# 9-Pin_Mini_DIN_Breakout_PCB_v1.net
KiCad netlist of a schematic drawn in EAGLE
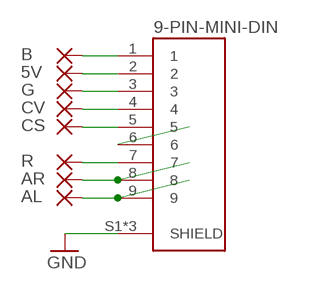
[diagram p0: schematic, sheet 1]

(export (version "E")
  (design (tool "Eeschema 10.0.6"))
  (components
    (comp (ref "5V")
      (value "PADSRECTANGLE-1,27X2,54")
      (footprint "eagle-import:RECTANGLE-1,27X2,54")
      (libsource (lib "eagle-import") (part "PADSRECTANGLE-1,27X2,54"))
    )
    (comp (ref "9-PIN-MINI-DIN")
      (value "9-PIN-MINI-DIN")
      (footprint "eagle-import:9-PIN-MINI-DIN")
      (libsource (lib "eagle-import") (part "9-PIN-MINI-DIN"))
    )
    (comp (ref "AL")
      (value "PADSRECTANGLE-1,27X2,54")
      (footprint "eagle-import:RECTANGLE-1,27X2,54")
      (libsource (lib "eagle-import") (part "PADSRECTANGLE-1,27X2,54"))
    )
    (comp (ref "AR")
      (value "PADSRECTANGLE-1,27X2,54")
      (footprint "eagle-import:RECTANGLE-1,27X2,54")
      (libsource (lib "eagle-import") (part "PADSRECTANGLE-1,27X2,54"))
    )
    (comp (ref "B")
      (value "PADSRECTANGLE-1,27X2,54")
      (footprint "eagle-import:RECTANGLE-1,27X2,54")
      (libsource (lib "eagle-import") (part "PADSRECTANGLE-1,27X2,54"))
    )
    (comp (ref "CS")
      (value "PADSRECTANGLE-1,27X2,54")
      (footprint "eagle-import:RECTANGLE-1,27X2,54")
      (libsource (lib "eagle-import") (part "PADSRECTANGLE-1,27X2,54"))
    )
    (comp (ref "CV")
      (value "PADSRECTANGLE-1,27X2,54")
      (footprint "eagle-import:RECTANGLE-1,27X2,54")
      (libsource (lib "eagle-import") (part "PADSRECTANGLE-1,27X2,54"))
    )
    (comp (ref "G")
      (value "PADSRECTANGLE-1,27X2,54")
      (footprint "eagle-import:RECTANGLE-1,27X2,54")
      (libsource (lib "eagle-import") (part "PADSRECTANGLE-1,27X2,54"))
    )
    (comp (ref "R")
      (value "PADSRECTANGLE-1,27X2,54")
      (footprint "eagle-import:RECTANGLE-1,27X2,54")
      (libsource (lib "eagle-import") (part "PADSRECTANGLE-1,27X2,54"))
    )
  )
  (nets
    (net (code "1") (name "GND") (class "Default")
      (node (ref "9-PIN-MINI-DIN") (pin "S1") (pinfunction "SHIELD_S1") (pintype "passive"))
      (node (ref "9-PIN-MINI-DIN") (pin "S2") (pinfunction "SHIELD_S2") (pintype "passive"))
      (node (ref "9-PIN-MINI-DIN") (pin "S3") (pinfunction "SHIELD_S3") (pintype "passive"))
    )
    (net (code "2") (name "Net-(5V-P)") (class "Default")
      (node (ref "5V") (pin "1") (pinfunction "P_1") (pintype "passive"))
      (node (ref "9-PIN-MINI-DIN") (pin "2") (pinfunction "2_2") (pintype "passive"))
    )
    (net (code "3") (name "Net-(AL-P)") (class "Default")
      (node (ref "9-PIN-MINI-DIN") (pin "9") (pinfunction "9_9") (pintype "passive"))
      (node (ref "AL") (pin "1") (pinfunction "P_1") (pintype "passive"))
    )
    (net (code "4") (name "Net-(AR-P)") (class "Default")
      (node (ref "9-PIN-MINI-DIN") (pin "8") (pinfunction "8_8") (pintype "passive"))
      (node (ref "AR") (pin "1") (pinfunction "P_1") (pintype "passive"))
    )
    (net (code "5") (name "Net-(B-P)") (class "Default")
      (node (ref "9-PIN-MINI-DIN") (pin "1") (pinfunction "1_1") (pintype "passive"))
      (node (ref "B") (pin "1") (pinfunction "P_1") (pintype "passive"))
    )
    (net (code "6") (name "Net-(CS-P)") (class "Default")
      (node (ref "9-PIN-MINI-DIN") (pin "5") (pinfunction "5_5") (pintype "passive"))
      (node (ref "CS") (pin "1") (pinfunction "P_1") (pintype "passive"))
    )
    (net (code "7") (name "Net-(CV-P)") (class "Default")
      (node (ref "9-PIN-MINI-DIN") (pin "4") (pinfunction "4_4") (pintype "passive"))
      (node (ref "CV") (pin "1") (pinfunction "P_1") (pintype "passive"))
    )
    (net (code "8") (name "Net-(G-P)") (class "Default")
      (node (ref "9-PIN-MINI-DIN") (pin "3") (pinfunction "3_3") (pintype "passive"))
      (node (ref "G") (pin "1") (pinfunction "P_1") (pintype "passive"))
    )
    (net (code "9") (name "Net-(R-P)") (class "Default")
      (node (ref "9-PIN-MINI-DIN") (pin "7") (pinfunction "7_7") (pintype "passive"))
      (node (ref "R") (pin "1") (pinfunction "P_1") (pintype "passive"))
    )
    (net (code "10") (name "unconnected-(9-PIN-MINI-DIN-Pad6)") (class "Default")
      (node (ref "9-PIN-MINI-DIN") (pin "6") (pinfunction "6_6") (pintype "passive"))
    )
  )
)
